# M106A.net
KiCad netlist of a schematic drawn in EAGLE
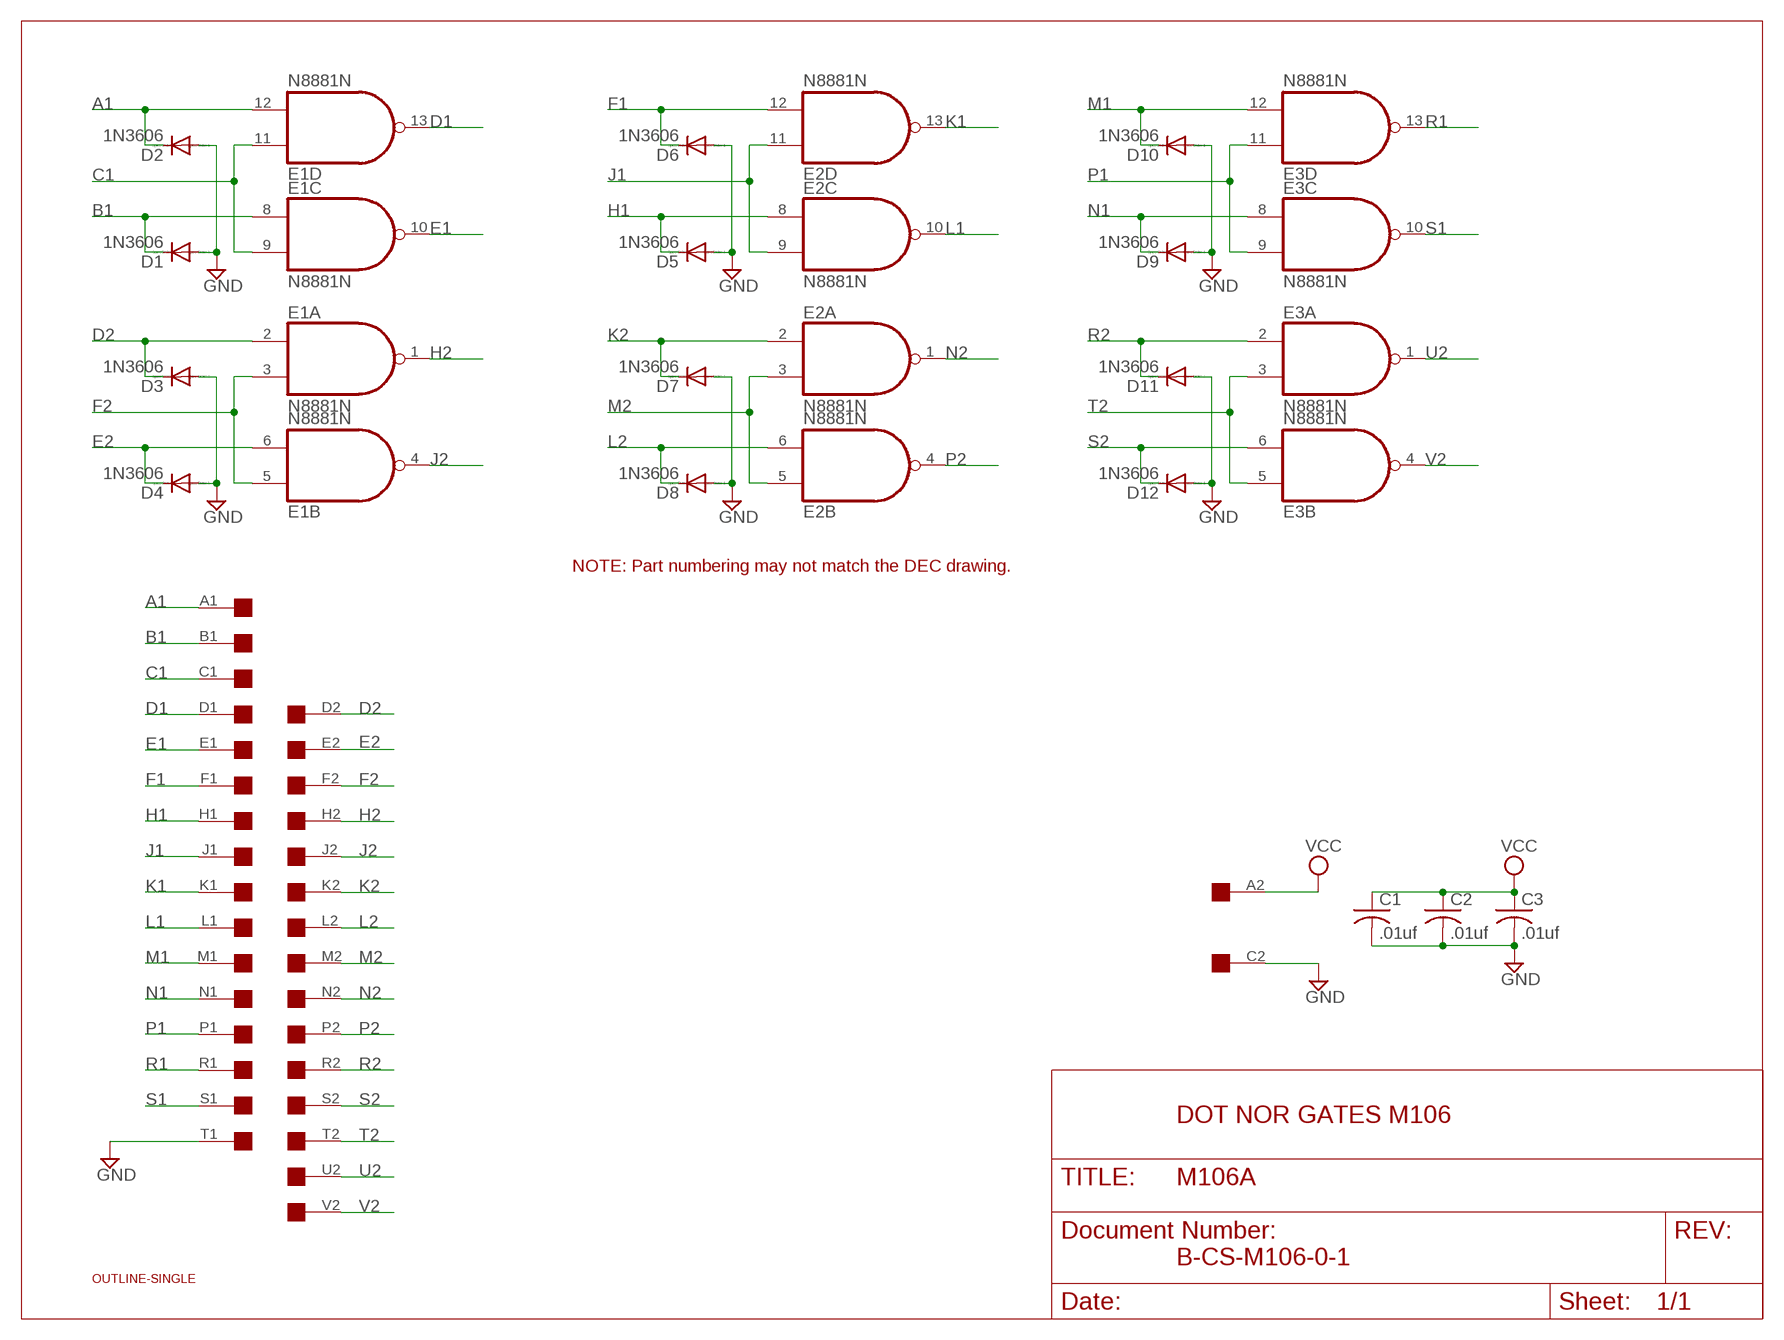
[diagram p0: schematic, sheet 1]

(export (version "E")
  (design (tool "Eeschema 10.0.6"))
  (components
    (comp (ref "C1")
      (value ".01uf")
      (footprint "eagle-import:C050-025X075")
      (libsource (lib "eagle-import") (part "C-US050-025X075"))
    )
    (comp (ref "C2")
      (value ".01uf")
      (footprint "eagle-import:C050-025X075")
      (libsource (lib "eagle-import") (part "C-US050-025X075"))
    )
    (comp (ref "C3")
      (value ".01uf")
      (footprint "eagle-import:C050-025X075")
      (libsource (lib "eagle-import") (part "C-US050-025X075"))
    )
    (comp (ref "D1")
      (value "1N3606")
      (footprint "eagle-import:DO35-10")
      (libsource (lib "eagle-import") (part "1N4148DO35-10"))
    )
    (comp (ref "D2")
      (value "1N3606")
      (footprint "eagle-import:DO35-10")
      (libsource (lib "eagle-import") (part "1N4148DO35-10"))
    )
    (comp (ref "D3")
      (value "1N3606")
      (footprint "eagle-import:DO35-10")
      (libsource (lib "eagle-import") (part "1N4148DO35-10"))
    )
    (comp (ref "D4")
      (value "1N3606")
      (footprint "eagle-import:DO35-10")
      (libsource (lib "eagle-import") (part "1N4148DO35-10"))
    )
    (comp (ref "D5")
      (value "1N3606")
      (footprint "eagle-import:DO35-10")
      (libsource (lib "eagle-import") (part "1N4148DO35-10"))
    )
    (comp (ref "D6")
      (value "1N3606")
      (footprint "eagle-import:DO35-10")
      (libsource (lib "eagle-import") (part "1N4148DO35-10"))
    )
    (comp (ref "D7")
      (value "1N3606")
      (footprint "eagle-import:DO35-10")
      (libsource (lib "eagle-import") (part "1N4148DO35-10"))
    )
    (comp (ref "D8")
      (value "1N3606")
      (footprint "eagle-import:DO35-10")
      (libsource (lib "eagle-import") (part "1N4148DO35-10"))
    )
    (comp (ref "D9")
      (value "1N3606")
      (footprint "eagle-import:DO35-10")
      (libsource (lib "eagle-import") (part "1N4148DO35-10"))
    )
    (comp (ref "D10")
      (value "1N3606")
      (footprint "eagle-import:DO35-10")
      (libsource (lib "eagle-import") (part "1N4148DO35-10"))
    )
    (comp (ref "D11")
      (value "1N3606")
      (footprint "eagle-import:DO35-10")
      (libsource (lib "eagle-import") (part "1N4148DO35-10"))
    )
    (comp (ref "D12")
      (value "1N3606")
      (footprint "eagle-import:DO35-10")
      (libsource (lib "eagle-import") (part "1N4148DO35-10"))
    )
    (comp (ref "E1")
      (value "N8881N")
      (footprint "eagle-import:DIL14")
      (libsource (lib "eagle-import") (part "N8881N"))
    )
    (comp (ref "E2")
      (value "N8881N")
      (footprint "eagle-import:DIL14")
      (libsource (lib "eagle-import") (part "N8881N"))
    )
    (comp (ref "E3")
      (value "N8881N")
      (footprint "eagle-import:DIL14")
      (libsource (lib "eagle-import") (part "N8881N"))
    )
    (comp (ref "U$1")
      (value "SINGLE")
      (footprint "eagle-import:EDGE-CON2")
      (libsource (lib "eagle-import") (part "SINGLE"))
    )
    (comp (ref "U$4")
      (value "OUTLINE-SINGLE")
      (footprint "eagle-import:SINGLE")
      (libsource (lib "eagle-import") (part "OUTLINE-SINGLE"))
    )
  )
  (nets
    (net (code "1") (name "/A1") (class "Default")
      (node (ref "D2") (pin "C") (pinfunction "C_C") (pintype "passive"))
      (node (ref "E1") (pin "12") (pinfunction "I1_12") (pintype "input"))
      (node (ref "U$1") (pin "A1") (pinfunction "1_A1") (pintype "bidirectional"))
    )
    (net (code "2") (name "/B1") (class "Default")
      (node (ref "D1") (pin "C") (pinfunction "C_C") (pintype "passive"))
      (node (ref "E1") (pin "8") (pinfunction "I0_8") (pintype "input"))
      (node (ref "U$1") (pin "B1") (pinfunction "1_B1") (pintype "bidirectional"))
    )
    (net (code "3") (name "/C1") (class "Default")
      (node (ref "E1") (pin "11") (pinfunction "I0_11") (pintype "input"))
      (node (ref "E1") (pin "9") (pinfunction "I1_9") (pintype "input"))
      (node (ref "U$1") (pin "C1") (pinfunction "1_C1") (pintype "bidirectional"))
    )
    (net (code "4") (name "/D1") (class "Default")
      (node (ref "E1") (pin "13") (pinfunction "O_13") (pintype "open_collector"))
      (node (ref "U$1") (pin "D1") (pinfunction "1_D1") (pintype "bidirectional"))
    )
    (net (code "5") (name "/D2") (class "Default")
      (node (ref "D3") (pin "C") (pinfunction "C_C") (pintype "passive"))
      (node (ref "E1") (pin "2") (pinfunction "I0_2") (pintype "input"))
      (node (ref "U$1") (pin "D2") (pinfunction "1_D2") (pintype "bidirectional"))
    )
    (net (code "6") (name "/E1") (class "Default")
      (node (ref "E1") (pin "10") (pinfunction "O_10") (pintype "open_collector"))
      (node (ref "U$1") (pin "E1") (pinfunction "1_E1") (pintype "bidirectional"))
    )
    (net (code "7") (name "/E2") (class "Default")
      (node (ref "D4") (pin "C") (pinfunction "C_C") (pintype "passive"))
      (node (ref "E1") (pin "6") (pinfunction "I1_6") (pintype "input"))
      (node (ref "U$1") (pin "E2") (pinfunction "1_E2") (pintype "bidirectional"))
    )
    (net (code "8") (name "/F1") (class "Default")
      (node (ref "D6") (pin "C") (pinfunction "C_C") (pintype "passive"))
      (node (ref "E2") (pin "12") (pinfunction "I1_12") (pintype "input"))
      (node (ref "U$1") (pin "F1") (pinfunction "1_F1") (pintype "bidirectional"))
    )
    (net (code "9") (name "/F2") (class "Default")
      (node (ref "E1") (pin "3") (pinfunction "I1_3") (pintype "input"))
      (node (ref "E1") (pin "5") (pinfunction "I0_5") (pintype "input"))
      (node (ref "U$1") (pin "F2") (pinfunction "1_F2") (pintype "bidirectional"))
    )
    (net (code "10") (name "/H1") (class "Default")
      (node (ref "D5") (pin "C") (pinfunction "C_C") (pintype "passive"))
      (node (ref "E2") (pin "8") (pinfunction "I0_8") (pintype "input"))
      (node (ref "U$1") (pin "H1") (pinfunction "1_H1") (pintype "bidirectional"))
    )
    (net (code "11") (name "/H2") (class "Default")
      (node (ref "E1") (pin "1") (pinfunction "O_1") (pintype "open_collector"))
      (node (ref "U$1") (pin "H2") (pinfunction "1_H2") (pintype "bidirectional"))
    )
    (net (code "12") (name "/J1") (class "Default")
      (node (ref "E2") (pin "11") (pinfunction "I0_11") (pintype "input"))
      (node (ref "E2") (pin "9") (pinfunction "I1_9") (pintype "input"))
      (node (ref "U$1") (pin "J1") (pinfunction "1_J1") (pintype "bidirectional"))
    )
    (net (code "13") (name "/J2") (class "Default")
      (node (ref "E1") (pin "4") (pinfunction "O_4") (pintype "open_collector"))
      (node (ref "U$1") (pin "J2") (pinfunction "1_J2") (pintype "bidirectional"))
    )
    (net (code "14") (name "/K1") (class "Default")
      (node (ref "E2") (pin "13") (pinfunction "O_13") (pintype "open_collector"))
      (node (ref "U$1") (pin "K1") (pinfunction "1_K1") (pintype "bidirectional"))
    )
    (net (code "15") (name "/K2") (class "Default")
      (node (ref "D7") (pin "C") (pinfunction "C_C") (pintype "passive"))
      (node (ref "E2") (pin "2") (pinfunction "I0_2") (pintype "input"))
      (node (ref "U$1") (pin "K2") (pinfunction "1_K2") (pintype "bidirectional"))
    )
    (net (code "16") (name "/L1") (class "Default")
      (node (ref "E2") (pin "10") (pinfunction "O_10") (pintype "open_collector"))
      (node (ref "U$1") (pin "L1") (pinfunction "1_L1") (pintype "bidirectional"))
    )
    (net (code "17") (name "/L2") (class "Default")
      (node (ref "D8") (pin "C") (pinfunction "C_C") (pintype "passive"))
      (node (ref "E2") (pin "6") (pinfunction "I1_6") (pintype "input"))
      (node (ref "U$1") (pin "L2") (pinfunction "1_L2") (pintype "bidirectional"))
    )
    (net (code "18") (name "/M1") (class "Default")
      (node (ref "D10") (pin "C") (pinfunction "C_C") (pintype "passive"))
      (node (ref "E3") (pin "12") (pinfunction "I1_12") (pintype "input"))
      (node (ref "U$1") (pin "M1") (pinfunction "1_M1") (pintype "bidirectional"))
    )
    (net (code "19") (name "/M2") (class "Default")
      (node (ref "E2") (pin "3") (pinfunction "I1_3") (pintype "input"))
      (node (ref "E2") (pin "5") (pinfunction "I0_5") (pintype "input"))
      (node (ref "U$1") (pin "M2") (pinfunction "1_M2") (pintype "bidirectional"))
    )
    (net (code "20") (name "/N1") (class "Default")
      (node (ref "D9") (pin "C") (pinfunction "C_C") (pintype "passive"))
      (node (ref "E3") (pin "8") (pinfunction "I0_8") (pintype "input"))
      (node (ref "U$1") (pin "N1") (pinfunction "1_N1") (pintype "bidirectional"))
    )
    (net (code "21") (name "/N2") (class "Default")
      (node (ref "E2") (pin "1") (pinfunction "O_1") (pintype "open_collector"))
      (node (ref "U$1") (pin "N2") (pinfunction "1_N2") (pintype "bidirectional"))
    )
    (net (code "22") (name "/P1") (class "Default")
      (node (ref "E3") (pin "11") (pinfunction "I0_11") (pintype "input"))
      (node (ref "E3") (pin "9") (pinfunction "I1_9") (pintype "input"))
      (node (ref "U$1") (pin "P1") (pinfunction "1_P1") (pintype "bidirectional"))
    )
    (net (code "23") (name "/P2") (class "Default")
      (node (ref "E2") (pin "4") (pinfunction "O_4") (pintype "open_collector"))
      (node (ref "U$1") (pin "P2") (pinfunction "1_P2") (pintype "bidirectional"))
    )
    (net (code "24") (name "/R1") (class "Default")
      (node (ref "E3") (pin "13") (pinfunction "O_13") (pintype "open_collector"))
      (node (ref "U$1") (pin "R1") (pinfunction "1_R1") (pintype "bidirectional"))
    )
    (net (code "25") (name "/R2") (class "Default")
      (node (ref "D11") (pin "C") (pinfunction "C_C") (pintype "passive"))
      (node (ref "E3") (pin "2") (pinfunction "I0_2") (pintype "input"))
      (node (ref "U$1") (pin "R2") (pinfunction "1_R2") (pintype "bidirectional"))
    )
    (net (code "26") (name "/S1") (class "Default")
      (node (ref "E3") (pin "10") (pinfunction "O_10") (pintype "open_collector"))
      (node (ref "U$1") (pin "S1") (pinfunction "1_S1") (pintype "bidirectional"))
    )
    (net (code "27") (name "/S2") (class "Default")
      (node (ref "D12") (pin "C") (pinfunction "C_C") (pintype "passive"))
      (node (ref "E3") (pin "6") (pinfunction "I1_6") (pintype "input"))
      (node (ref "U$1") (pin "S2") (pinfunction "1_S2") (pintype "bidirectional"))
    )
    (net (code "28") (name "/T2") (class "Default")
      (node (ref "E3") (pin "3") (pinfunction "I1_3") (pintype "input"))
      (node (ref "E3") (pin "5") (pinfunction "I0_5") (pintype "input"))
      (node (ref "U$1") (pin "T2") (pinfunction "1_T2") (pintype "bidirectional"))
    )
    (net (code "29") (name "/U2") (class "Default")
      (node (ref "E3") (pin "1") (pinfunction "O_1") (pintype "open_collector"))
      (node (ref "U$1") (pin "U2") (pinfunction "1_U2") (pintype "bidirectional"))
    )
    (net (code "30") (name "/V2") (class "Default")
      (node (ref "E3") (pin "4") (pinfunction "O_4") (pintype "open_collector"))
      (node (ref "U$1") (pin "V2") (pinfunction "1_V2") (pintype "bidirectional"))
    )
    (net (code "31") (name "GND") (class "Default")
      (node (ref "C1") (pin "2") (pinfunction "2_2") (pintype "passive"))
      (node (ref "C2") (pin "2") (pinfunction "2_2") (pintype "passive"))
      (node (ref "C3") (pin "2") (pinfunction "2_2") (pintype "passive"))
      (node (ref "D1") (pin "A") (pinfunction "A_A") (pintype "passive"))
      (node (ref "D10") (pin "A") (pinfunction "A_A") (pintype "passive"))
      (node (ref "D11") (pin "A") (pinfunction "A_A") (pintype "passive"))
      (node (ref "D12") (pin "A") (pinfunction "A_A") (pintype "passive"))
      (node (ref "D2") (pin "A") (pinfunction "A_A") (pintype "passive"))
      (node (ref "D3") (pin "A") (pinfunction "A_A") (pintype "passive"))
      (node (ref "D4") (pin "A") (pinfunction "A_A") (pintype "passive"))
      (node (ref "D5") (pin "A") (pinfunction "A_A") (pintype "passive"))
      (node (ref "D6") (pin "A") (pinfunction "A_A") (pintype "passive"))
      (node (ref "D7") (pin "A") (pinfunction "A_A") (pintype "passive"))
      (node (ref "D8") (pin "A") (pinfunction "A_A") (pintype "passive"))
      (node (ref "D9") (pin "A") (pinfunction "A_A") (pintype "passive"))
      (node (ref "U$1") (pin "C2") (pinfunction "1_C2") (pintype "bidirectional"))
      (node (ref "U$1") (pin "T1") (pinfunction "1_T1") (pintype "bidirectional"))
    )
    (net (code "32") (name "VCC") (class "Default")
      (node (ref "C1") (pin "1") (pinfunction "1_1") (pintype "passive"))
      (node (ref "C2") (pin "1") (pinfunction "1_1") (pintype "passive"))
      (node (ref "C3") (pin "1") (pinfunction "1_1") (pintype "passive"))
      (node (ref "U$1") (pin "A2") (pinfunction "1_A2") (pintype "bidirectional"))
    )
  )
)
